# w15_node2.net
KiCad netlist of a schematic drawn in EAGLE
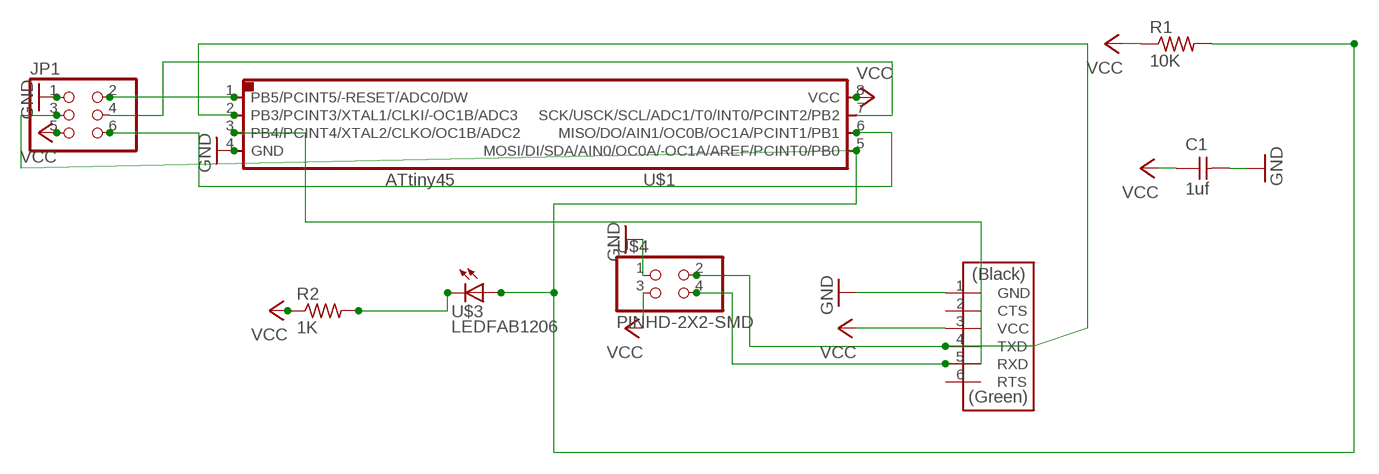
[diagram p0: schematic, sheet 1]

(export (version "E")
  (design (tool "Eeschema 10.0.6"))
  (components
    (comp (ref "C1")
      (value "1uf")
      (footprint "eagle-import:C1206FAB")
      (libsource (lib "eagle-import") (part "CAP-UNPOLARIZEDFAB"))
    )
    (comp (ref "JP1")
      (value "PINHD-2X3-SMD")
      (footprint "eagle-import:2X03SMD")
      (libsource (lib "eagle-import") (part "PINHD-2X3-SMD"))
    )
    (comp (ref "R1")
      (value "10K")
      (footprint "eagle-import:R1206FAB")
      (libsource (lib "eagle-import") (part "RES-US1206FAB"))
    )
    (comp (ref "R2")
      (value "1K")
      (footprint "eagle-import:R1206FAB")
      (libsource (lib "eagle-import") (part "RES-US1206FAB"))
    )
    (comp (ref "U$1")
      (value "ATTINY45SI")
      (footprint "eagle-import:SOIC8")
      (libsource (lib "eagle-import") (part "ATTINY45SI"))
    )
    (comp (ref "U$2")
      (value "FTDI-SMD-HEADER")
      (footprint "eagle-import:1X06SMD")
      (libsource (lib "eagle-import") (part "FTDI-SMD-HEADER"))
    )
    (comp (ref "U$3")
      (value "LEDFAB1206")
      (footprint "eagle-import:LED1206FAB")
      (libsource (lib "eagle-import") (part "LEDFAB1206"))
    )
    (comp (ref "U$4")
      (value "PINHD-2X2-SMD")
      (footprint "eagle-import:2X02SMD")
      (libsource (lib "eagle-import") (part "PINHD-2X2-SMD"))
    )
  )
  (nets
    (net (code "1") (name "GND") (class "Default")
      (node (ref "C1") (pin "2") (pinfunction "2_2") (pintype "passive"))
      (node (ref "JP1") (pin "1") (pinfunction "1_1") (pintype "passive"))
      (node (ref "U$1") (pin "4") (pinfunction "GND_4") (pintype "bidirectional"))
      (node (ref "U$2") (pin "1") (pinfunction "GND_1") (pintype "bidirectional"))
      (node (ref "U$4") (pin "1") (pinfunction "1_1") (pintype "passive"))
    )
    (net (code "2") (name "Net-(U$1-MISO{slash}DO{slash}AIN1{slash}OC0B{slash}OC1A{slash}PCINT1{slash}PB1)") (class "Default")
      (node (ref "JP1") (pin "6") (pinfunction "6_6") (pintype "passive"))
      (node (ref "U$1") (pin "6") (pinfunction "MISO/DO/AIN1/OC0B/OC1A/PCINT1/PB1_6") (pintype "bidirectional"))
    )
    (net (code "3") (name "Net-(U$1-MOSI{slash}DI{slash}SDA{slash}AIN0{slash}OC0A{slash}-OC1A{slash}AREF{slash}PCINT0{slash}PB0)") (class "Default")
      (node (ref "JP1") (pin "3") (pinfunction "3_3") (pintype "passive"))
      (node (ref "R1") (pin "2") (pinfunction "2_2") (pintype "passive"))
      (node (ref "U$1") (pin "5") (pinfunction "MOSI/DI/SDA/AIN0/OC0A/-OC1A/AREF/PCINT0/PB0_5") (pintype "bidirectional"))
      (node (ref "U$3") (pin "1") (pinfunction "A_1") (pintype "passive"))
    )
    (net (code "4") (name "Net-(U$1-PB3{slash}PCINT3{slash}XTAL1{slash}CLKI{slash}-OC1B{slash}ADC3)") (class "Default")
      (node (ref "U$1") (pin "2") (pinfunction "PB3/PCINT3/XTAL1/CLKI/-OC1B/ADC3_2") (pintype "bidirectional"))
      (node (ref "U$2") (pin "4") (pinfunction "TXD_4") (pintype "bidirectional"))
      (node (ref "U$4") (pin "2") (pinfunction "2_2") (pintype "passive"))
    )
    (net (code "5") (name "Net-(U$1-PB4{slash}PCINT4{slash}XTAL2{slash}CLKO{slash}OC1B{slash}ADC2)") (class "Default")
      (node (ref "U$1") (pin "3") (pinfunction "PB4/PCINT4/XTAL2/CLKO/OC1B/ADC2_3") (pintype "bidirectional"))
      (node (ref "U$2") (pin "5") (pinfunction "RXD_5") (pintype "bidirectional"))
      (node (ref "U$4") (pin "4") (pinfunction "4_4") (pintype "passive"))
    )
    (net (code "6") (name "Net-(U$1-PB5{slash}PCINT5{slash}-RESET{slash}ADC0{slash}DW)") (class "Default")
      (node (ref "JP1") (pin "2") (pinfunction "2_2") (pintype "passive"))
      (node (ref "U$1") (pin "1") (pinfunction "PB5/PCINT5/-RESET/ADC0/DW_1") (pintype "bidirectional"))
    )
    (net (code "7") (name "Net-(U$1-SCK{slash}USCK{slash}SCL{slash}ADC1{slash}T0{slash}INT0{slash}PCINT2{slash}PB2)") (class "Default")
      (node (ref "JP1") (pin "4") (pinfunction "4_4") (pintype "passive"))
      (node (ref "U$1") (pin "7") (pinfunction "SCK/USCK/SCL/ADC1/T0/INT0/PCINT2/PB2_7") (pintype "bidirectional"))
    )
    (net (code "8") (name "Net-(U$3-C)") (class "Default")
      (node (ref "R2") (pin "2") (pinfunction "2_2") (pintype "passive"))
      (node (ref "U$3") (pin "2") (pinfunction "C_2") (pintype "passive"))
    )
    (net (code "9") (name "VCC") (class "Default")
      (node (ref "C1") (pin "1") (pinfunction "1_1") (pintype "passive"))
      (node (ref "JP1") (pin "5") (pinfunction "5_5") (pintype "passive"))
      (node (ref "R1") (pin "1") (pinfunction "1_1") (pintype "passive"))
      (node (ref "R2") (pin "1") (pinfunction "1_1") (pintype "passive"))
      (node (ref "U$1") (pin "8") (pinfunction "VCC_8") (pintype "bidirectional"))
      (node (ref "U$2") (pin "3") (pinfunction "VCC_3") (pintype "bidirectional"))
      (node (ref "U$4") (pin "3") (pinfunction "3_3") (pintype "passive"))
    )
    (net (code "10") (name "unconnected-(U$2-CTS-Pad2)") (class "Default")
      (node (ref "U$2") (pin "2") (pinfunction "CTS_2") (pintype "bidirectional"))
    )
    (net (code "11") (name "unconnected-(U$2-RTS-Pad6)") (class "Default")
      (node (ref "U$2") (pin "6") (pinfunction "RTS_6") (pintype "bidirectional"))
    )
  )
)
